# CH340K.net
KiCad netlist of a schematic drawn in Altium Designer
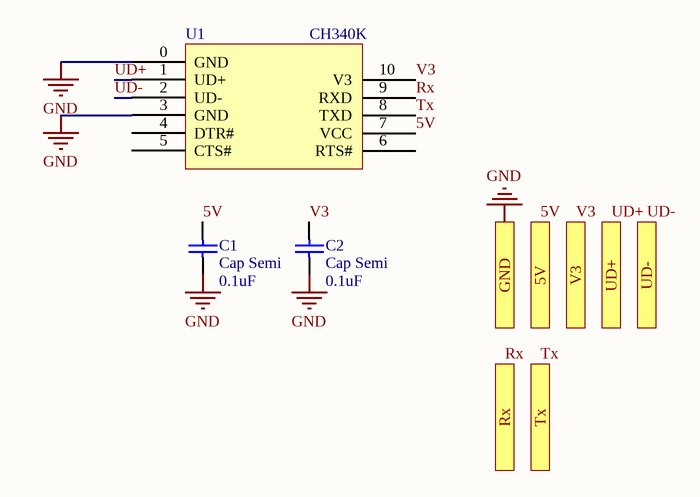
[diagram p0: CH340K.SchDoc]

(export (version "E")
  (design (tool "Eeschema 10.0.6"))
  (components
    (comp (ref "C1")
      (value "Cap Semi")
      (footprint "1608[0603]")
      (description "Capacitor (Semiconductor SIM Model)")
      (fields (field (name "ALTIUM_VALUE") "0.1uF") (field (name "PUBLISHER") "Altium Limited"))
      (libsource (lib "Miscellaneous Devices") (part "Cap Semi"))
    )
    (comp (ref "C2")
      (value "Cap Semi")
      (footprint "1608[0603]")
      (description "Capacitor (Semiconductor SIM Model)")
      (fields (field (name "ALTIUM_VALUE") "0.1uF") (field (name "PUBLISHER") "Altium Limited"))
      (libsource (lib "Miscellaneous Devices") (part "Cap Semi"))
    )
    (comp (ref "U1")
      (value "CH340K")
      (footprint "ESSOP-10")
      (libsource (lib "Components_myself") (part "CH340K"))
    )
  )
  (nets
    (net (code "1") (name "/5V") (class "Default")
      (node (ref "C1") (pin "1") (pinfunction "1_1") (pintype "passive"))
      (node (ref "U1") (pin "7") (pinfunction "VCC_7") (pintype "passive"))
    )
    (net (code "2") (name "/Rx") (class "Default")
      (node (ref "U1") (pin "9") (pinfunction "RXD_9") (pintype "passive"))
    )
    (net (code "3") (name "/Tx") (class "Default")
      (node (ref "U1") (pin "8") (pinfunction "TXD_8") (pintype "passive"))
    )
    (net (code "4") (name "/UD+") (class "Default")
      (node (ref "U1") (pin "1") (pinfunction "UD+_1") (pintype "passive"))
    )
    (net (code "5") (name "/UD-") (class "Default")
      (node (ref "U1") (pin "2") (pinfunction "UD-_2") (pintype "passive"))
    )
    (net (code "6") (name "/V3") (class "Default")
      (node (ref "C2") (pin "1") (pinfunction "1_1") (pintype "passive"))
      (node (ref "U1") (pin "10") (pinfunction "V3_10") (pintype "passive"))
    )
    (net (code "7") (name "GND") (class "Default")
      (node (ref "C1") (pin "2") (pinfunction "2_2") (pintype "passive"))
      (node (ref "C2") (pin "2") (pinfunction "2_2") (pintype "passive"))
      (node (ref "U1") (pin "0") (pinfunction "GND_0") (pintype "passive"))
      (node (ref "U1") (pin "3") (pinfunction "GND_3") (pintype "passive"))
    )
    (net (code "8") (name "unconnected-(U1-CTS#-Pad5)") (class "Default")
      (node (ref "U1") (pin "5") (pinfunction "CTS#_5") (pintype "passive"))
    )
    (net (code "9") (name "unconnected-(U1-DTR#-Pad4)") (class "Default")
      (node (ref "U1") (pin "4") (pinfunction "DTR#_4") (pintype "passive"))
    )
    (net (code "10") (name "unconnected-(U1-RTS#-Pad6)") (class "Default")
      (node (ref "U1") (pin "6") (pinfunction "RTS#_6") (pintype "passive"))
    )
  )
)
